# GDEnvSensorNode_1_4h.net
KiCad netlist of a schematic drawn in EAGLE
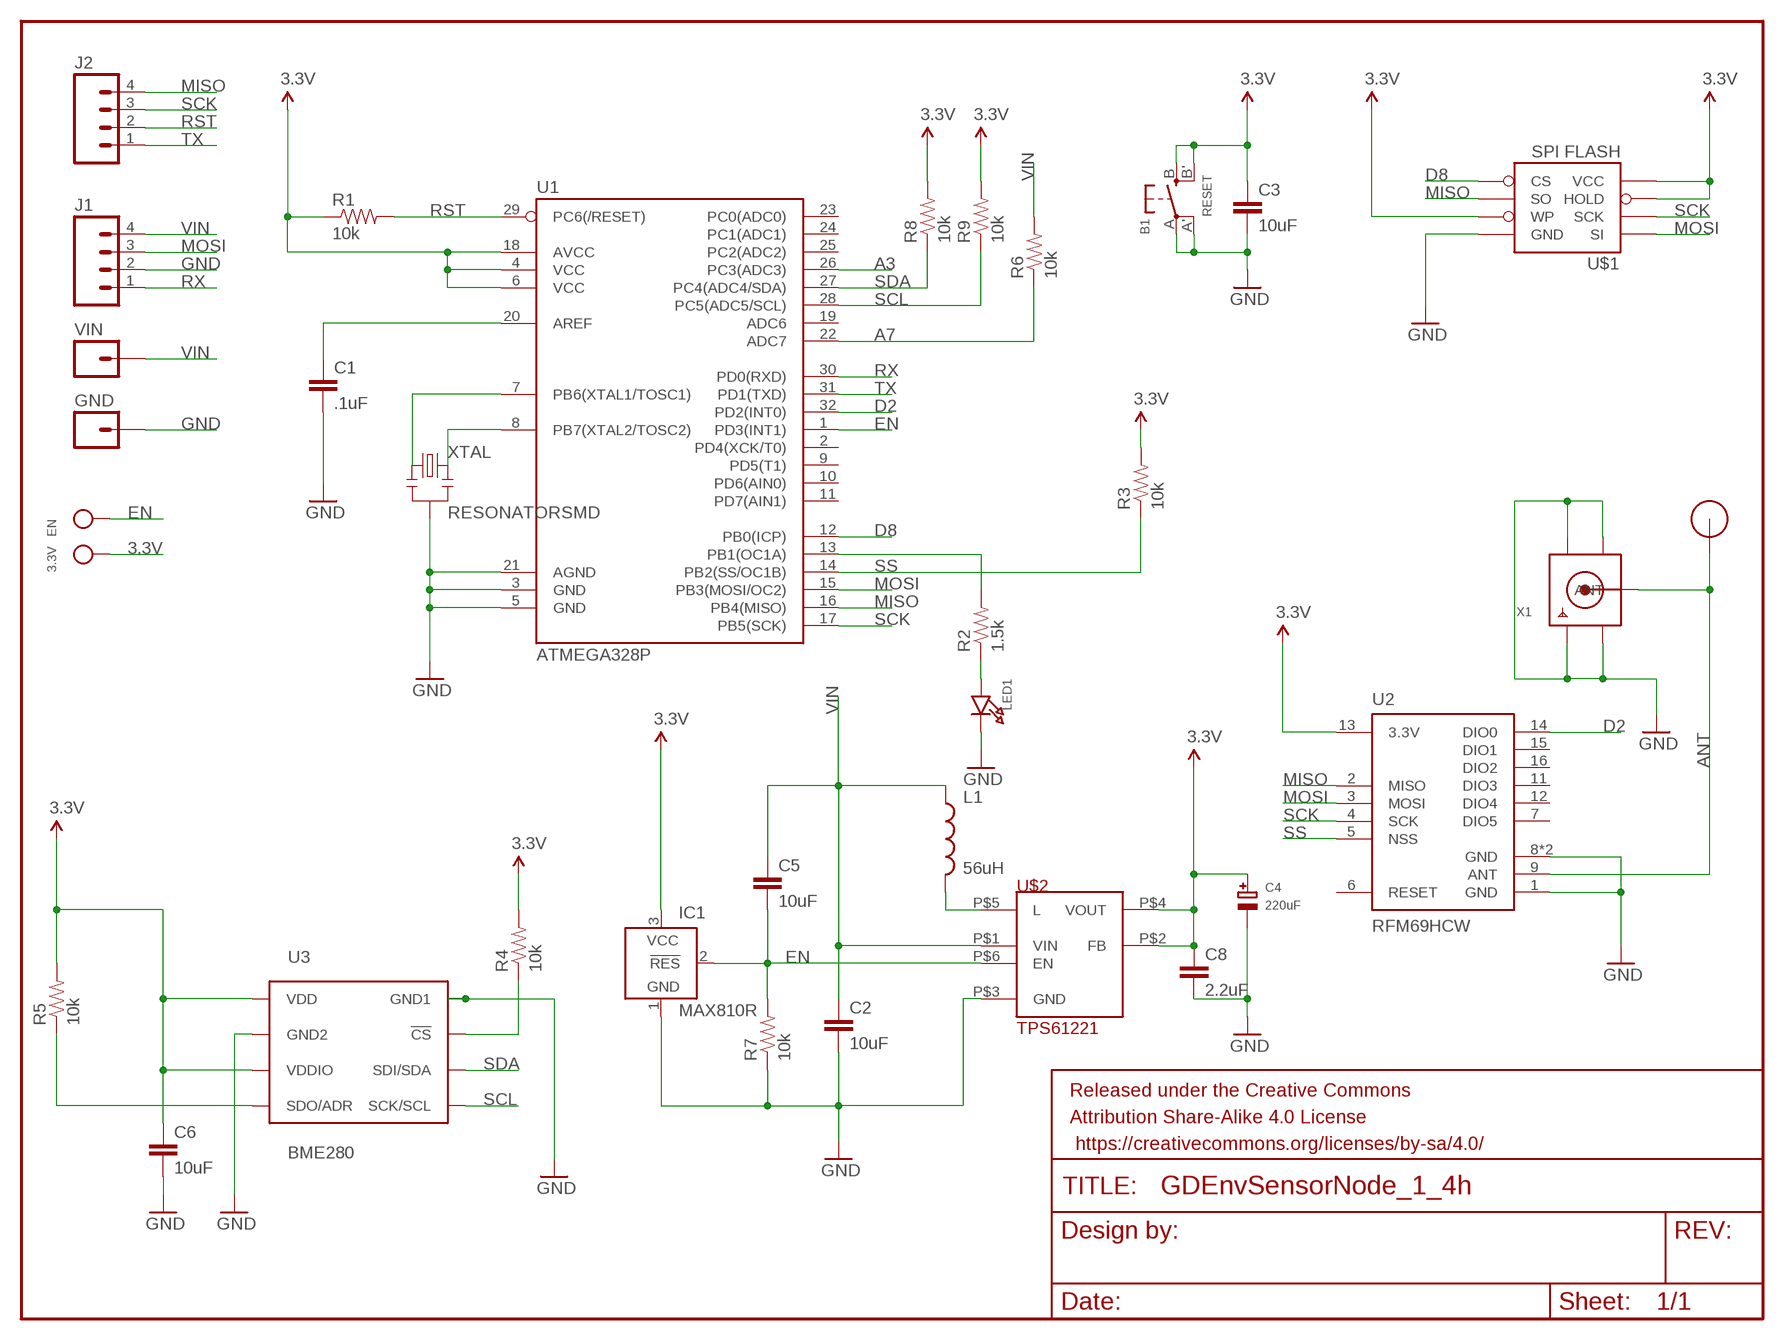
[diagram p0: schematic, sheet 1]

(export (version "E")
  (design (tool "Eeschema 10.0.6"))
  (components
    (comp (ref "3.3V")
      (value "TESTPOINTROUND1MM")
      (footprint "eagle-import:TESTPOINT_ROUND_1MM")
      (libsource (lib "eagle-import") (part "TESTPOINTROUND1MM"))
    )
    (comp (ref "B1")
      (value "RESET")
      (footprint "eagle-import:BTN_KMR2_4.6X2.8")
      (libsource (lib "eagle-import") (part "SWITCH_TACT_SMT4.6X2.8"))
    )
    (comp (ref "C1")
      (value ".1uF")
      (footprint "eagle-import:0805")
      (libsource (lib "eagle-import") (part "CAP0805"))
    )
    (comp (ref "C2")
      (value "10uF")
      (footprint "eagle-import:0805")
      (libsource (lib "eagle-import") (part "CAP0805"))
    )
    (comp (ref "C3")
      (value "10uF")
      (footprint "eagle-import:0805")
      (libsource (lib "eagle-import") (part "CAP0805"))
    )
    (comp (ref "C4")
      (value "220uF")
      (footprint "eagle-import:EIA7343-31_D-R")
      (libsource (lib "eagle-import") (part "CAP_TANTALUMD/7343_REFLOW"))
    )
    (comp (ref "C5")
      (value "10uF")
      (footprint "eagle-import:0805")
      (libsource (lib "eagle-import") (part "CAP0805"))
    )
    (comp (ref "C6")
      (value "10uF")
      (footprint "eagle-import:0805")
      (libsource (lib "eagle-import") (part "CAP0805"))
    )
    (comp (ref "C8")
      (value "2.2uF")
      (footprint "eagle-import:0805")
      (libsource (lib "eagle-import") (part "CAP0805"))
    )
    (comp (ref "EN")
      (value "TESTPOINTROUND1MM")
      (footprint "eagle-import:TESTPOINT_ROUND_1MM")
      (libsource (lib "eagle-import") (part "TESTPOINTROUND1MM"))
    )
    (comp (ref "FRAME1")
      (value "FRAME-LETTER")
      (footprint "eagle-import:CREATIVE_COMMONS")
      (libsource (lib "eagle-import") (part "FRAME-LETTER"))
    )
    (comp (ref "GND")
      (value "M01PTH_2MM")
      (footprint "eagle-import:1X01_2MM")
      (libsource (lib "eagle-import") (part "M01PTH_2MM"))
    )
    (comp (ref "IC1")
      (value "MAX810R")
      (footprint "eagle-import:SOT23B-3")
      (fields (field (name "MF") "MICROCHIP") (field (name "MPN") "TCM809MENB713"))
      (libsource (lib "eagle-import") (part "TCM809"))
    )
    (comp (ref "J1")
      (value "M04PTH")
      (footprint "eagle-import:1X04")
      (libsource (lib "eagle-import") (part "M04PTH"))
    )
    (comp (ref "J2")
      (value "M04PTH")
      (footprint "eagle-import:1X04")
      (libsource (lib "eagle-import") (part "M04PTH"))
    )
    (comp (ref "L1")
      (value "56uH")
      (footprint "eagle-import:3MM")
      (libsource (lib "eagle-import") (part "INDUCTOR3MM"))
    )
    (comp (ref "LED1")
      (value "LED0805")
      (footprint "eagle-import:CHIPLED_0805")
      (libsource (lib "eagle-import") (part "LED0805"))
    )
    (comp (ref "R1")
      (value "10k")
      (footprint "eagle-import:0805")
      (libsource (lib "eagle-import") (part "RESISTOR0805-RES"))
    )
    (comp (ref "R2")
      (value "1.5k")
      (footprint "eagle-import:0805")
      (libsource (lib "eagle-import") (part "RESISTOR0805-RES"))
    )
    (comp (ref "R3")
      (value "10k")
      (footprint "eagle-import:0805")
      (libsource (lib "eagle-import") (part "RESISTOR0805-RES"))
    )
    (comp (ref "R4")
      (value "10k")
      (footprint "eagle-import:0805")
      (libsource (lib "eagle-import") (part "RESISTOR0805-RES"))
    )
    (comp (ref "R5")
      (value "10k")
      (footprint "eagle-import:0805")
      (libsource (lib "eagle-import") (part "RESISTOR0805-RES"))
    )
    (comp (ref "R6")
      (value "10k")
      (footprint "eagle-import:0805")
      (libsource (lib "eagle-import") (part "RESISTOR0805-RES"))
    )
    (comp (ref "R7")
      (value "10k")
      (footprint "eagle-import:0805")
      (libsource (lib "eagle-import") (part "RESISTOR0805-RES"))
    )
    (comp (ref "R8")
      (value "10k")
      (footprint "eagle-import:0805")
      (libsource (lib "eagle-import") (part "RESISTOR0805-RES"))
    )
    (comp (ref "R9")
      (value "10k")
      (footprint "eagle-import:0805")
      (libsource (lib "eagle-import") (part "RESISTOR0805-RES"))
    )
    (comp (ref "U$1")
      (value "SPI FLASH")
      (footprint "eagle-import:SO08")
      (libsource (lib "eagle-import") (part "AT25F512BJEDEC_3.9MM"))
    )
    (comp (ref "U$2")
      (value "TPS61221")
      (footprint "eagle-import:TPS61221")
      (fields (field (name "MF") "Texas Instruments"))
      (libsource (lib "eagle-import") (part "TPS61221"))
    )
    (comp (ref "U$4")
      (value "RFM12B_ANTENNA")
      (footprint "eagle-import:RFM12B-ANTENNA")
      (libsource (lib "eagle-import") (part "RFM12B_ANTENNA"))
    )
    (comp (ref "U1")
      (value "ATMEGA328P")
      (footprint "eagle-import:TQFP32-08")
      (libsource (lib "eagle-import") (part "ATMEGA328P_TQFP"))
    )
    (comp (ref "U2")
      (value "RFM69HCW")
      (footprint "eagle-import:RFM69HCW-XXXS2")
      (libsource (lib "eagle-import") (part "RFM69HCW"))
    )
    (comp (ref "U3")
      (value "BME280")
      (footprint "eagle-import:BME280_LGA")
      (libsource (lib "eagle-import") (part "BME280"))
    )
    (comp (ref "VIN")
      (value "M01PTH_2MM")
      (footprint "eagle-import:1X01_2MM")
      (libsource (lib "eagle-import") (part "M01PTH_2MM"))
    )
    (comp (ref "X1")
      (value "SMACONNECTOR_EDGE_UFL")
      (footprint "eagle-import:SMA_EDGELAUNCH_UFL")
      (libsource (lib "eagle-import") (part "SMACONNECTOR_EDGE_UFL"))
    )
    (comp (ref "XTAL")
      (value "RESONATORSMD")
      (footprint "eagle-import:RESONATOR-SMD")
      (libsource (lib "eagle-import") (part "RESONATORSMD"))
    )
  )
  (nets
    (net (code "1") (name "/A3") (class "Default")
      (node (ref "U1") (pin "26") (pinfunction "PC3(ADC3)_26") (pintype "bidirectional"))
    )
    (net (code "2") (name "/A7") (class "Default")
      (node (ref "R6") (pin "1") (pinfunction "1_1") (pintype "passive"))
      (node (ref "U1") (pin "22") (pinfunction "ADC7_22") (pintype "bidirectional"))
    )
    (net (code "3") (name "/ANT") (class "Default")
      (node (ref "U$4") (pin "P$1") (pinfunction "1_P$1") (pintype "bidirectional"))
      (node (ref "U2") (pin "9") (pinfunction "ANT_9") (pintype "passive"))
      (node (ref "X1") (pin "P") (pinfunction "ANT_P") (pintype "bidirectional"))
    )
    (net (code "4") (name "/D2") (class "Default")
      (node (ref "U1") (pin "32") (pinfunction "PD2(INT0)_32") (pintype "bidirectional"))
      (node (ref "U2") (pin "14") (pinfunction "DIO0_14") (pintype "bidirectional"))
    )
    (net (code "5") (name "/D8") (class "Default")
      (node (ref "U$1") (pin "1_CS") (pinfunction "CS_1_CS") (pintype "bidirectional"))
      (node (ref "U1") (pin "12") (pinfunction "PB0(ICP)_12") (pintype "bidirectional"))
    )
    (net (code "6") (name "/EN") (class "Default")
      (node (ref "C5") (pin "2") (pinfunction "2_2") (pintype "passive"))
      (node (ref "EN") (pin "P$1") (pinfunction "P$1_P$1") (pintype "bidirectional"))
      (node (ref "IC1") (pin "2") (pinfunction "~{RES}_2") (pintype "output"))
      (node (ref "R7") (pin "2") (pinfunction "2_2") (pintype "passive"))
      (node (ref "U$2") (pin "P$6") (pinfunction "EN_P$6") (pintype "bidirectional"))
      (node (ref "U1") (pin "1") (pinfunction "PD3(INT1)_1") (pintype "bidirectional"))
    )
    (net (code "7") (name "/MISO") (class "Default")
      (node (ref "J2") (pin "4") (pinfunction "4_4") (pintype "passive"))
      (node (ref "U$1") (pin "2_SO") (pinfunction "SO_2_SO") (pintype "bidirectional"))
      (node (ref "U1") (pin "16") (pinfunction "PB4(MISO)_16") (pintype "bidirectional"))
      (node (ref "U2") (pin "2") (pinfunction "MISO_2") (pintype "bidirectional"))
    )
    (net (code "8") (name "/MOSI") (class "Default")
      (node (ref "J1") (pin "3") (pinfunction "3_3") (pintype "passive"))
      (node (ref "U$1") (pin "5_SI") (pinfunction "SI_5_SI") (pintype "bidirectional"))
      (node (ref "U1") (pin "15") (pinfunction "PB3(MOSI/OC2)_15") (pintype "bidirectional"))
      (node (ref "U2") (pin "3") (pinfunction "MOSI_3") (pintype "input"))
    )
    (net (code "9") (name "/RST") (class "Default")
      (node (ref "J2") (pin "2") (pinfunction "2_2") (pintype "passive"))
      (node (ref "R1") (pin "2") (pinfunction "2_2") (pintype "passive"))
      (node (ref "U1") (pin "29") (pinfunction "PC6(/RESET)_29") (pintype "bidirectional"))
    )
    (net (code "10") (name "/RX") (class "Default")
      (node (ref "J1") (pin "1") (pinfunction "1_1") (pintype "passive"))
      (node (ref "U1") (pin "30") (pinfunction "PD0(RXD)_30") (pintype "bidirectional"))
    )
    (net (code "11") (name "/SCK") (class "Default")
      (node (ref "J2") (pin "3") (pinfunction "3_3") (pintype "passive"))
      (node (ref "U$1") (pin "6_SCK") (pinfunction "SCK_6_SCK") (pintype "bidirectional"))
      (node (ref "U1") (pin "17") (pinfunction "PB5(SCK)_17") (pintype "bidirectional"))
      (node (ref "U2") (pin "4") (pinfunction "SCK_4") (pintype "input"))
    )
    (net (code "12") (name "/SCL") (class "Default")
      (node (ref "R9") (pin "1") (pinfunction "1_1") (pintype "passive"))
      (node (ref "U1") (pin "28") (pinfunction "PC5(ADC5/SCL)_28") (pintype "bidirectional"))
      (node (ref "U3") (pin "P$4") (pinfunction "SCK/SCL_P$4") (pintype "bidirectional"))
    )
    (net (code "13") (name "/SDA") (class "Default")
      (node (ref "R8") (pin "1") (pinfunction "1_1") (pintype "passive"))
      (node (ref "U1") (pin "27") (pinfunction "PC4(ADC4/SDA)_27") (pintype "bidirectional"))
      (node (ref "U3") (pin "P$3") (pinfunction "SDI/SDA_P$3") (pintype "bidirectional"))
    )
    (net (code "14") (name "/SS") (class "Default")
      (node (ref "R3") (pin "1") (pinfunction "1_1") (pintype "passive"))
      (node (ref "U1") (pin "14") (pinfunction "PB2(SS/OC1B)_14") (pintype "bidirectional"))
      (node (ref "U2") (pin "5") (pinfunction "NSS_5") (pintype "input"))
    )
    (net (code "15") (name "/TX") (class "Default")
      (node (ref "J2") (pin "1") (pinfunction "1_1") (pintype "passive"))
      (node (ref "U1") (pin "31") (pinfunction "PD1(TXD)_31") (pintype "bidirectional"))
    )
    (net (code "16") (name "/VIN") (class "Default")
      (node (ref "C2") (pin "1") (pinfunction "1_1") (pintype "passive"))
      (node (ref "C5") (pin "1") (pinfunction "1_1") (pintype "passive"))
      (node (ref "J1") (pin "4") (pinfunction "4_4") (pintype "passive"))
      (node (ref "L1") (pin "P$1") (pinfunction "1_P$1") (pintype "passive"))
      (node (ref "R6") (pin "2") (pinfunction "2_2") (pintype "passive"))
      (node (ref "U$2") (pin "P$1") (pinfunction "VIN_P$1") (pintype "bidirectional"))
      (node (ref "VIN") (pin "1") (pinfunction "1_1") (pintype "passive"))
    )
    (net (code "17") (name "3.3V") (class "Default")
      (node (ref "3.3V") (pin "P$1") (pinfunction "P$1_P$1") (pintype "bidirectional"))
      (node (ref "B1") (pin "B") (pinfunction "S_B") (pintype "passive"))
      (node (ref "B1") (pin "B'") (pinfunction "S1_B'") (pintype "passive"))
      (node (ref "C3") (pin "1") (pinfunction "1_1") (pintype "passive"))
      (node (ref "C4") (pin "+") (pinfunction "+_+") (pintype "passive"))
      (node (ref "C6") (pin "1") (pinfunction "1_1") (pintype "passive"))
      (node (ref "C8") (pin "1") (pinfunction "1_1") (pintype "passive"))
      (node (ref "IC1") (pin "3") (pinfunction "VCC_3") (pintype "power_in"))
      (node (ref "R1") (pin "1") (pinfunction "1_1") (pintype "passive"))
      (node (ref "R3") (pin "2") (pinfunction "2_2") (pintype "passive"))
      (node (ref "R4") (pin "2") (pinfunction "2_2") (pintype "passive"))
      (node (ref "R5") (pin "2") (pinfunction "2_2") (pintype "passive"))
      (node (ref "R8") (pin "2") (pinfunction "2_2") (pintype "passive"))
      (node (ref "R9") (pin "2") (pinfunction "2_2") (pintype "passive"))
      (node (ref "U$1") (pin "3_WP") (pinfunction "WP_3_WP") (pintype "bidirectional"))
      (node (ref "U$1") (pin "7_HOLD") (pinfunction "HOLD_7_HOLD") (pintype "bidirectional"))
      (node (ref "U$1") (pin "8_VCC") (pinfunction "VCC_8_VCC") (pintype "bidirectional"))
      (node (ref "U$2") (pin "P$2") (pinfunction "FB_P$2") (pintype "bidirectional"))
      (node (ref "U$2") (pin "P$4") (pinfunction "VOUT_P$4") (pintype "bidirectional"))
      (node (ref "U1") (pin "18") (pinfunction "AVCC_18") (pintype "bidirectional"))
      (node (ref "U1") (pin "4") (pinfunction "VCC_4") (pintype "bidirectional"))
      (node (ref "U1") (pin "6") (pinfunction "VCC_6") (pintype "bidirectional"))
      (node (ref "U2") (pin "13") (pinfunction "3.3V_13") (pintype "power_in"))
      (node (ref "U3") (pin "P$6") (pinfunction "VDDIO_P$6") (pintype "bidirectional"))
      (node (ref "U3") (pin "P$8") (pinfunction "VDD_P$8") (pintype "bidirectional"))
    )
    (net (code "18") (name "GND") (class "Default")
      (node (ref "B1") (pin "A") (pinfunction "P_A") (pintype "passive"))
      (node (ref "B1") (pin "A'") (pinfunction "P1_A'") (pintype "passive"))
      (node (ref "C1") (pin "2") (pinfunction "2_2") (pintype "passive"))
      (node (ref "C2") (pin "2") (pinfunction "2_2") (pintype "passive"))
      (node (ref "C3") (pin "2") (pinfunction "2_2") (pintype "passive"))
      (node (ref "C4") (pin "-") (pinfunction "-_-") (pintype "passive"))
      (node (ref "C6") (pin "2") (pinfunction "2_2") (pintype "passive"))
      (node (ref "C8") (pin "2") (pinfunction "2_2") (pintype "passive"))
      (node (ref "GND") (pin "1") (pinfunction "1_1") (pintype "passive"))
      (node (ref "IC1") (pin "1") (pinfunction "GND_1") (pintype "power_in"))
      (node (ref "J1") (pin "2") (pinfunction "2_2") (pintype "passive"))
      (node (ref "LED1") (pin "C") (pinfunction "C_C") (pintype "passive"))
      (node (ref "R7") (pin "1") (pinfunction "1_1") (pintype "passive"))
      (node (ref "U$1") (pin "4_GND") (pinfunction "GND_4_GND") (pintype "bidirectional"))
      (node (ref "U$2") (pin "P$3") (pinfunction "GND_P$3") (pintype "bidirectional"))
      (node (ref "U1") (pin "21") (pinfunction "AGND_21") (pintype "bidirectional"))
      (node (ref "U1") (pin "3") (pinfunction "GND_3") (pintype "bidirectional"))
      (node (ref "U1") (pin "5") (pinfunction "GND_5") (pintype "bidirectional"))
      (node (ref "U2") (pin "1") (pinfunction "GND_1") (pintype "power_in"))
      (node (ref "U2") (pin "10") (pinfunction "GND_10") (pintype "power_in"))
      (node (ref "U2") (pin "8") (pinfunction "GND_8") (pintype "power_in"))
      (node (ref "U3") (pin "P$1") (pinfunction "GND1_P$1") (pintype "bidirectional"))
      (node (ref "U3") (pin "P$7") (pinfunction "GND2_P$7") (pintype "bidirectional"))
      (node (ref "X1") (pin "GND@1") (pinfunction "GND1_GND@1") (pintype "power_in"))
      (node (ref "X1") (pin "GND@2") (pinfunction "GND2_GND@2") (pintype "power_in"))
      (node (ref "X1") (pin "GND@3") (pinfunction "GND3_GND@3") (pintype "power_in"))
      (node (ref "X1") (pin "GND@4") (pinfunction "GND4_GND@4") (pintype "power_in"))
      (node (ref "XTAL") (pin "2") (pinfunction "2_2") (pintype "passive"))
    )
    (net (code "19") (name "Net-(L1-2)") (class "Default")
      (node (ref "L1") (pin "P$2") (pinfunction "2_P$2") (pintype "passive"))
      (node (ref "U$2") (pin "P$5") (pinfunction "L_P$5") (pintype "bidirectional"))
    )
    (net (code "20") (name "Net-(LED1-PadA)") (class "Default")
      (node (ref "LED1") (pin "A") (pinfunction "A_A") (pintype "passive"))
      (node (ref "R2") (pin "1") (pinfunction "1_1") (pintype "passive"))
    )
    (net (code "21") (name "Net-(U1-AREF)") (class "Default")
      (node (ref "C1") (pin "1") (pinfunction "1_1") (pintype "passive"))
      (node (ref "U1") (pin "20") (pinfunction "AREF_20") (pintype "bidirectional"))
    )
    (net (code "22") (name "Net-(U1-PB1(OC1A))") (class "Default")
      (node (ref "R2") (pin "2") (pinfunction "2_2") (pintype "passive"))
      (node (ref "U1") (pin "13") (pinfunction "PB1(OC1A)_13") (pintype "bidirectional"))
    )
    (net (code "23") (name "Net-(U1-PB6(XTAL1{slash}TOSC1))") (class "Default")
      (node (ref "U1") (pin "7") (pinfunction "PB6(XTAL1/TOSC1)_7") (pintype "bidirectional"))
      (node (ref "XTAL") (pin "1") (pinfunction "1_1") (pintype "passive"))
    )
    (net (code "24") (name "Net-(U1-PB7(XTAL2{slash}TOSC2))") (class "Default")
      (node (ref "U1") (pin "8") (pinfunction "PB7(XTAL2/TOSC2)_8") (pintype "bidirectional"))
      (node (ref "XTAL") (pin "3") (pinfunction "3_3") (pintype "passive"))
    )
    (net (code "25") (name "Net-(U3-SDO{slash}ADR)") (class "Default")
      (node (ref "R5") (pin "1") (pinfunction "1_1") (pintype "passive"))
      (node (ref "U3") (pin "P$5") (pinfunction "SDO/ADR_P$5") (pintype "bidirectional"))
    )
    (net (code "26") (name "Net-(U3-~{CS})") (class "Default")
      (node (ref "R4") (pin "1") (pinfunction "1_1") (pintype "passive"))
      (node (ref "U3") (pin "P$2") (pinfunction "~{CS}_P$2") (pintype "bidirectional"))
    )
    (net (code "27") (name "unconnected-(U1-ADC6-Pad19)") (class "Default")
      (node (ref "U1") (pin "19") (pinfunction "ADC6_19") (pintype "bidirectional"))
    )
    (net (code "28") (name "unconnected-(U1-PC0(ADC0)-Pad23)") (class "Default")
      (node (ref "U1") (pin "23") (pinfunction "PC0(ADC0)_23") (pintype "bidirectional"))
    )
    (net (code "29") (name "unconnected-(U1-PC1(ADC1)-Pad24)") (class "Default")
      (node (ref "U1") (pin "24") (pinfunction "PC1(ADC1)_24") (pintype "bidirectional"))
    )
    (net (code "30") (name "unconnected-(U1-PC2(ADC2)-Pad25)") (class "Default")
      (node (ref "U1") (pin "25") (pinfunction "PC2(ADC2)_25") (pintype "bidirectional"))
    )
    (net (code "31") (name "unconnected-(U1-PD4(XCK{slash}T0)-Pad2)") (class "Default")
      (node (ref "U1") (pin "2") (pinfunction "PD4(XCK/T0)_2") (pintype "bidirectional"))
    )
    (net (code "32") (name "unconnected-(U1-PD5(T1)-Pad9)") (class "Default")
      (node (ref "U1") (pin "9") (pinfunction "PD5(T1)_9") (pintype "bidirectional"))
    )
    (net (code "33") (name "unconnected-(U1-PD6(AIN0)-Pad10)") (class "Default")
      (node (ref "U1") (pin "10") (pinfunction "PD6(AIN0)_10") (pintype "bidirectional"))
    )
    (net (code "34") (name "unconnected-(U1-PD7(AIN1)-Pad11)") (class "Default")
      (node (ref "U1") (pin "11") (pinfunction "PD7(AIN1)_11") (pintype "bidirectional"))
    )
    (net (code "35") (name "unconnected-(U2-DIO1-Pad15)") (class "Default")
      (node (ref "U2") (pin "15") (pinfunction "DIO1_15") (pintype "bidirectional"))
    )
    (net (code "36") (name "unconnected-(U2-DIO2-Pad16)") (class "Default")
      (node (ref "U2") (pin "16") (pinfunction "DIO2_16") (pintype "bidirectional"))
    )
    (net (code "37") (name "unconnected-(U2-DIO3-Pad11)") (class "Default")
      (node (ref "U2") (pin "11") (pinfunction "DIO3_11") (pintype "bidirectional"))
    )
    (net (code "38") (name "unconnected-(U2-DIO4-Pad12)") (class "Default")
      (node (ref "U2") (pin "12") (pinfunction "DIO4_12") (pintype "bidirectional"))
    )
    (net (code "39") (name "unconnected-(U2-DIO5-Pad7)") (class "Default")
      (node (ref "U2") (pin "7") (pinfunction "DIO5_7") (pintype "bidirectional"))
    )
    (net (code "40") (name "unconnected-(U2-RESET-Pad6)") (class "Default")
      (node (ref "U2") (pin "6") (pinfunction "RESET_6") (pintype "input"))
    )
  )
)
